# SCH_RTC.net
KiCad netlist of a schematic drawn in Altium Designer
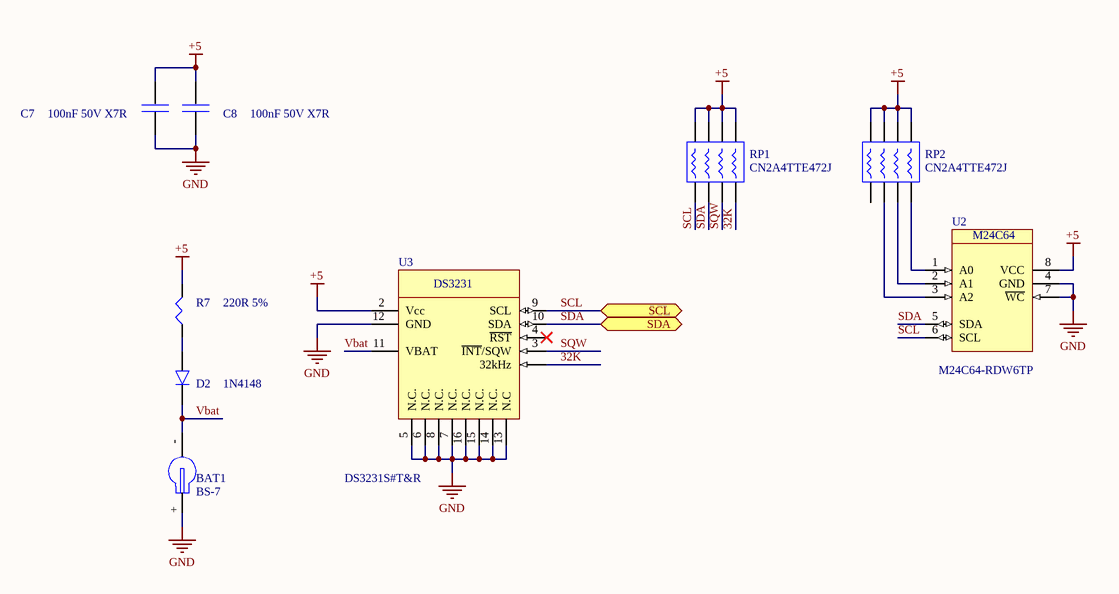
[diagram p0: SCH_RTC.SchDoc]

(export (version "E")
  (design (tool "Eeschema 10.0.6"))
  (components
    (comp (ref "BAT1")
      (value "BS-7")
      (description "Porta Pila CR2032")
      (libsource (lib "SCH_LIB") (part "BATT"))
    )
    (comp (ref "C7")
      (value "100nF 50V X7R")
      (footprint "C_0805")
      (description "100nF x 50v")
      (libsource (lib "SCH_LIB") (part "Capacitor"))
    )
    (comp (ref "C8")
      (value "100nF 50V X7R")
      (footprint "C_0805")
      (description "100nF x 50v")
      (libsource (lib "SCH_LIB") (part "Capacitor"))
    )
    (comp (ref "D2") (value "1N4148") (description "Signal Diode") (libsource (lib "SCH_LIB") (part "Diode")))
    (comp (ref "R7") (value "220R 5%") (footprint "R_0805") (libsource (lib "SCH_LIB") (part "Resistor")))
    (comp (ref "RP1") (value "CN2A4TTE472J") (libsource (lib "SCH_LIB") (part "Resistor_PACK")))
    (comp (ref "RP2") (value "CN2A4TTE472J") (libsource (lib "SCH_LIB") (part "Resistor_PACK")))
    (comp (ref "U2") (value "M24C64-RDW6TP") (libsource (lib "SCH_LIB") (part "EEPROM")))
    (comp (ref "U3")
      (value "DS3231S#T&R")
      (description "Real Time Clock")
      (libsource (lib "SCH_LIB") (part "DS3231"))
    )
  )
  (nets
    (net (code "1") (name "+5") (class "Default")
      (node (ref "C7") (pin "39") (pinfunction "39_39") (pintype "passive"))
      (node (ref "C8") (pin "39") (pinfunction "39_39") (pintype "passive"))
      (node (ref "R7") (pin "48") (pinfunction "48_48") (pintype "passive"))
      (node (ref "RP1") (pin "1") (pinfunction "1_1") (pintype "passive"))
      (node (ref "RP1") (pin "3") (pinfunction "3_3") (pintype "passive"))
      (node (ref "RP1") (pin "5") (pinfunction "5_5") (pintype "passive"))
      (node (ref "RP1") (pin "7") (pinfunction "7_7") (pintype "passive"))
      (node (ref "RP2") (pin "1") (pinfunction "1_1") (pintype "passive"))
      (node (ref "RP2") (pin "3") (pinfunction "3_3") (pintype "passive"))
      (node (ref "RP2") (pin "5") (pinfunction "5_5") (pintype "passive"))
      (node (ref "RP2") (pin "7") (pinfunction "7_7") (pintype "passive"))
      (node (ref "U2") (pin "8") (pinfunction "VCC_8") (pintype "power_in"))
      (node (ref "U3") (pin "2") (pinfunction "Vcc_2") (pintype "power_in"))
    )
    (net (code "2") (name "/32K") (class "Default")
      (node (ref "RP1") (pin "8") (pinfunction "8_8") (pintype "passive"))
      (node (ref "U3") (pin "1") (pinfunction "32kHz_1") (pintype "input"))
    )
    (net (code "3") (name "/SCL") (class "Default")
      (node (ref "RP1") (pin "2") (pinfunction "2_2") (pintype "passive"))
      (node (ref "U2") (pin "6") (pinfunction "SCL_6") (pintype "bidirectional"))
      (node (ref "U3") (pin "9") (pinfunction "SCL_9") (pintype "bidirectional"))
    )
    (net (code "4") (name "/SDA") (class "Default")
      (node (ref "RP1") (pin "4") (pinfunction "4_4") (pintype "passive"))
      (node (ref "U2") (pin "5") (pinfunction "SDA_5") (pintype "bidirectional"))
      (node (ref "U3") (pin "10") (pinfunction "SDA_10") (pintype "bidirectional"))
    )
    (net (code "5") (name "/SQW") (class "Default")
      (node (ref "RP1") (pin "6") (pinfunction "6_6") (pintype "passive"))
      (node (ref "U3") (pin "3") (pinfunction "~{INT}/SQW_3") (pintype "input"))
    )
    (net (code "6") (name "/Vbat") (class "Default")
      (node (ref "BAT1") (pin "-") (pinfunction "2_-") (pintype "passive"))
      (node (ref "D2") (pin "35") (pinfunction "35_35") (pintype "passive"))
      (node (ref "U3") (pin "11") (pinfunction "VBAT_11") (pintype "power_in"))
    )
    (net (code "7") (name "GND") (class "Default")
      (node (ref "BAT1") (pin "+") (pinfunction "1_+") (pintype "passive"))
      (node (ref "C7") (pin "38") (pinfunction "38_38") (pintype "passive"))
      (node (ref "C8") (pin "38") (pinfunction "38_38") (pintype "passive"))
      (node (ref "U2") (pin "4") (pinfunction "GND_4") (pintype "power_in"))
      (node (ref "U2") (pin "7") (pinfunction "~{WC}_7") (pintype "input"))
      (node (ref "U3") (pin "12") (pinfunction "GND_12") (pintype "power_in"))
      (node (ref "U3") (pin "13") (pinfunction "N.C_13") (pintype "passive"))
      (node (ref "U3") (pin "14") (pinfunction "N.C._14") (pintype "passive"))
      (node (ref "U3") (pin "15") (pinfunction "N.C._15") (pintype "passive"))
      (node (ref "U3") (pin "16") (pinfunction "N.C._16") (pintype "passive"))
      (node (ref "U3") (pin "5") (pinfunction "N.C._5") (pintype "passive"))
      (node (ref "U3") (pin "6") (pinfunction "N.C._6") (pintype "passive"))
      (node (ref "U3") (pin "7") (pinfunction "N.C._7") (pintype "passive"))
      (node (ref "U3") (pin "8") (pinfunction "N.C._8") (pintype "passive"))
    )
    (net (code "8") (name "Net-(D2-Pad34)") (class "Default")
      (node (ref "D2") (pin "34") (pinfunction "34_34") (pintype "passive"))
      (node (ref "R7") (pin "47") (pinfunction "47_47") (pintype "passive"))
    )
    (net (code "9") (name "Net-(U2-A0)") (class "Default")
      (node (ref "RP2") (pin "8") (pinfunction "8_8") (pintype "passive"))
      (node (ref "U2") (pin "1") (pinfunction "A0_1") (pintype "input"))
    )
    (net (code "10") (name "Net-(U2-A1)") (class "Default")
      (node (ref "RP2") (pin "6") (pinfunction "6_6") (pintype "passive"))
      (node (ref "U2") (pin "2") (pinfunction "A1_2") (pintype "input"))
    )
    (net (code "11") (name "Net-(U2-A2)") (class "Default")
      (node (ref "RP2") (pin "4") (pinfunction "4_4") (pintype "passive"))
      (node (ref "U2") (pin "3") (pinfunction "A2_3") (pintype "input"))
    )
    (net (code "12") (name "unconnected-(RP2-Pad2)") (class "Default")
      (node (ref "RP2") (pin "2") (pinfunction "2_2") (pintype "passive"))
    )
    (net (code "13") (name "unconnected-(U3-~{RST}-Pad4)") (class "Default")
      (node (ref "U3") (pin "4") (pinfunction "~{RST}_4") (pintype "input+no_connect"))
    )
  )
)
